# Heater.net
KiCad netlist of a schematic drawn in Altium Designer
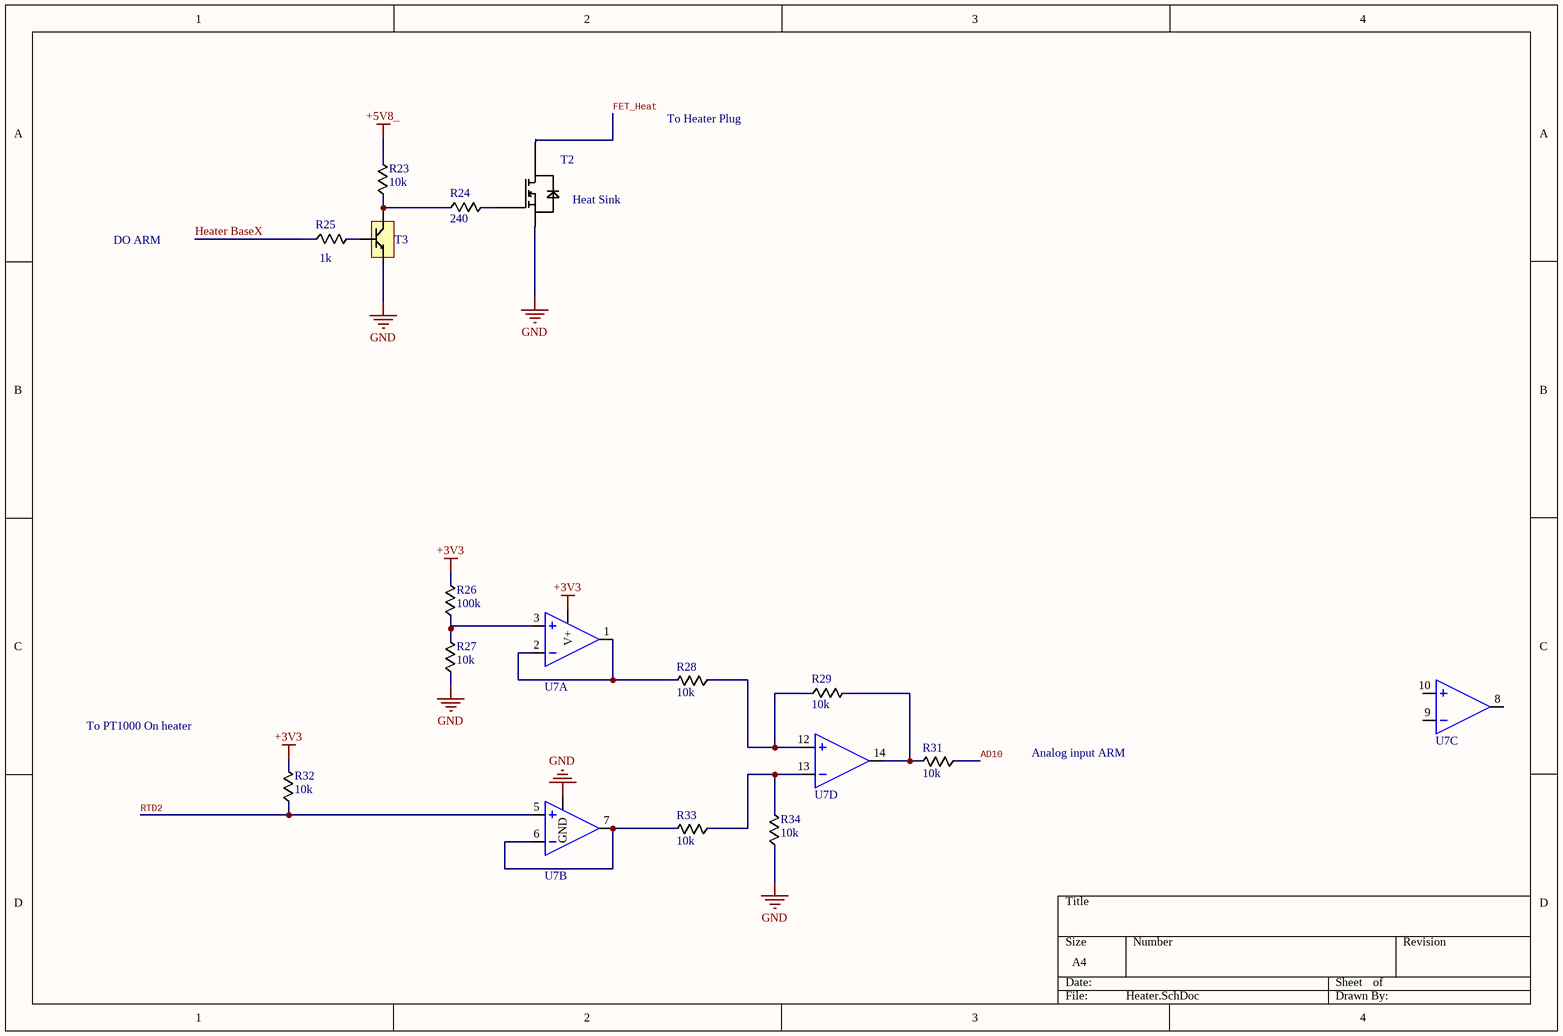
[diagram p0: Heater.SchDoc]

(export (version "E")
  (design (tool "Eeschema 10.0.6"))
  (components
    (comp (ref "R23")
      (value "10k")
      (footprint "0603")
      (description "RC0603FR-078K2")
      (libsource (lib "kontr") (part "Resistor 0805"))
    )
    (comp (ref "R24")
      (value "240")
      (footprint "0603")
      (description "RC0603FR-078K2")
      (libsource (lib "kontr") (part "Resistor 0805"))
    )
    (comp (ref "R25")
      (value "1k")
      (footprint "0603")
      (description "RC0603FR-078K2")
      (libsource (lib "kontr") (part "Resistor 0805"))
    )
    (comp (ref "R26")
      (value "100k")
      (footprint "0603")
      (description "RC0603FR-078K2")
      (libsource (lib "kontr") (part "Resistor 0805"))
    )
    (comp (ref "R27")
      (value "10k")
      (footprint "0603")
      (description "RC0603FR-078K2")
      (libsource (lib "kontr") (part "Resistor 0805"))
    )
    (comp (ref "R28")
      (value "10k")
      (footprint "0603")
      (description "RC0603FR-078K2")
      (libsource (lib "kontr") (part "Resistor 0805"))
    )
    (comp (ref "R29")
      (value "10k")
      (footprint "0603")
      (description "RC0603FR-078K2")
      (libsource (lib "kontr") (part "Resistor 0805"))
    )
    (comp (ref "R31")
      (value "10k")
      (footprint "0603")
      (description "RC0603FR-078K2")
      (libsource (lib "kontr") (part "Resistor 0805"))
    )
    (comp (ref "R32")
      (value "10k")
      (footprint "0603")
      (description "RC0603FR-078K2")
      (libsource (lib "kontr") (part "Resistor 0805"))
    )
    (comp (ref "R33")
      (value "10k")
      (footprint "0603")
      (description "RC0603FR-078K2")
      (libsource (lib "kontr") (part "Resistor 0805"))
    )
    (comp (ref "R34")
      (value "10k")
      (footprint "0603")
      (description "RC0603FR-078K2")
      (libsource (lib "kontr") (part "Resistor 0805"))
    )
    (comp (ref "T2")
      (value "IRFL024Npbf")
      (footprint "SOT223")
      (libsource (lib "kontr") (part "IRFL024Npbf"))
    )
    (comp (ref "T3") (value "mmbt3904") (footprint "SOT23") (libsource (lib "kontr") (part "mmbt3904")))
    (comp (ref "U7")
      (value "LM324DT")
      (footprint "SOIC 14 lead")
      (description "OPAMP")
      (libsource (lib "kontr") (part "MCP609"))
    )
  )
  (nets
    (net (code "1") (name "+3V3") (class "Default")
      (node (ref "R26") (pin "2") (pintype "passive"))
      (node (ref "R32") (pin "2") (pintype "passive"))
      (node (ref "U7") (pin "4") (pinfunction "V+_4") (pintype "passive"))
    )
    (net (code "2") (name "+5V8_") (class "Default") (node (ref "R23") (pin "2") (pintype "passive")))
    (net (code "3") (name "/AD10") (class "Default") (node (ref "R31") (pin "1") (pintype "passive")))
    (net (code "4") (name "/FET_Heat") (class "Default")
      (node (ref "T2") (pin "2") (pinfunction "D_2") (pintype "passive"))
    )
    (net (code "5") (name "/Heater BaseX") (class "Default") (node (ref "R25") (pin "1") (pintype "passive")))
    (net (code "6") (name "/RTD2") (class "Default")
      (node (ref "R32") (pin "1") (pintype "passive"))
      (node (ref "U7") (pin "5") (pinfunction "+IN_5") (pintype "passive"))
    )
    (net (code "7") (name "GND") (class "Default")
      (node (ref "R27") (pin "1") (pintype "passive"))
      (node (ref "R34") (pin "1") (pintype "passive"))
      (node (ref "T2") (pin "3") (pinfunction "S_3") (pintype "passive"))
      (node (ref "T3") (pin "2") (pinfunction "2_2") (pintype "passive"))
      (node (ref "U7") (pin "11") (pinfunction "GND_11") (pintype "passive"))
    )
    (net (code "8") (name "Net-(R23-Pad1)") (class "Default")
      (node (ref "R23") (pin "1") (pintype "passive"))
      (node (ref "R24") (pin "1") (pintype "passive"))
      (node (ref "T3") (pin "3") (pinfunction "3_3") (pintype "passive"))
    )
    (net (code "9") (name "Net-(R25-Pad2)") (class "Default")
      (node (ref "R25") (pin "2") (pintype "passive"))
      (node (ref "T3") (pin "1") (pinfunction "1_1") (pintype "passive"))
    )
    (net (code "10") (name "Net-(T2-G)") (class "Default")
      (node (ref "R24") (pin "2") (pintype "passive"))
      (node (ref "T2") (pin "1") (pinfunction "G_1") (pintype "passive"))
    )
    (net (code "11") (name "Net-(U7A-+IN)") (class "Default")
      (node (ref "R26") (pin "1") (pintype "passive"))
      (node (ref "R27") (pin "2") (pintype "passive"))
      (node (ref "U7") (pin "3") (pinfunction "+IN_3") (pintype "passive"))
    )
    (net (code "12") (name "Net-(U7A--IN)") (class "Default")
      (node (ref "R28") (pin "2") (pintype "passive"))
      (node (ref "U7") (pin "1") (pinfunction "OUT_1") (pintype "passive"))
      (node (ref "U7") (pin "2") (pinfunction "-IN_2") (pintype "passive"))
    )
    (net (code "13") (name "Net-(U7B--IN)") (class "Default")
      (node (ref "R33") (pin "2") (pintype "passive"))
      (node (ref "U7") (pin "6") (pinfunction "-IN_6") (pintype "passive"))
      (node (ref "U7") (pin "7") (pinfunction "OUT_7") (pintype "passive"))
    )
    (net (code "14") (name "Net-(U7D-+IN)") (class "Default")
      (node (ref "R28") (pin "1") (pintype "passive"))
      (node (ref "R29") (pin "1") (pintype "passive"))
      (node (ref "U7") (pin "12") (pinfunction "+IN_12") (pintype "passive"))
    )
    (net (code "15") (name "Net-(U7D--IN)") (class "Default")
      (node (ref "R33") (pin "1") (pintype "passive"))
      (node (ref "R34") (pin "2") (pintype "passive"))
      (node (ref "U7") (pin "13") (pinfunction "-IN_13") (pintype "passive"))
    )
    (net (code "16") (name "Net-(U7D-OUT)") (class "Default")
      (node (ref "R29") (pin "2") (pintype "passive"))
      (node (ref "R31") (pin "2") (pintype "passive"))
      (node (ref "U7") (pin "14") (pinfunction "OUT_14") (pintype "passive"))
    )
    (net (code "17") (name "unconnected-(U7C-+IN-Pad10)") (class "Default")
      (node (ref "U7") (pin "10") (pinfunction "+IN_10") (pintype "passive"))
    )
    (net (code "18") (name "unconnected-(U7C--IN-Pad9)") (class "Default")
      (node (ref "U7") (pin "9") (pinfunction "-IN_9") (pintype "passive"))
    )
    (net (code "19") (name "unconnected-(U7C-OUT-Pad8)") (class "Default")
      (node (ref "U7") (pin "8") (pinfunction "OUT_8") (pintype "passive"))
    )
  )
)
